# 60W_FM_PA.net
KiCad netlist of a schematic drawn in EAGLE
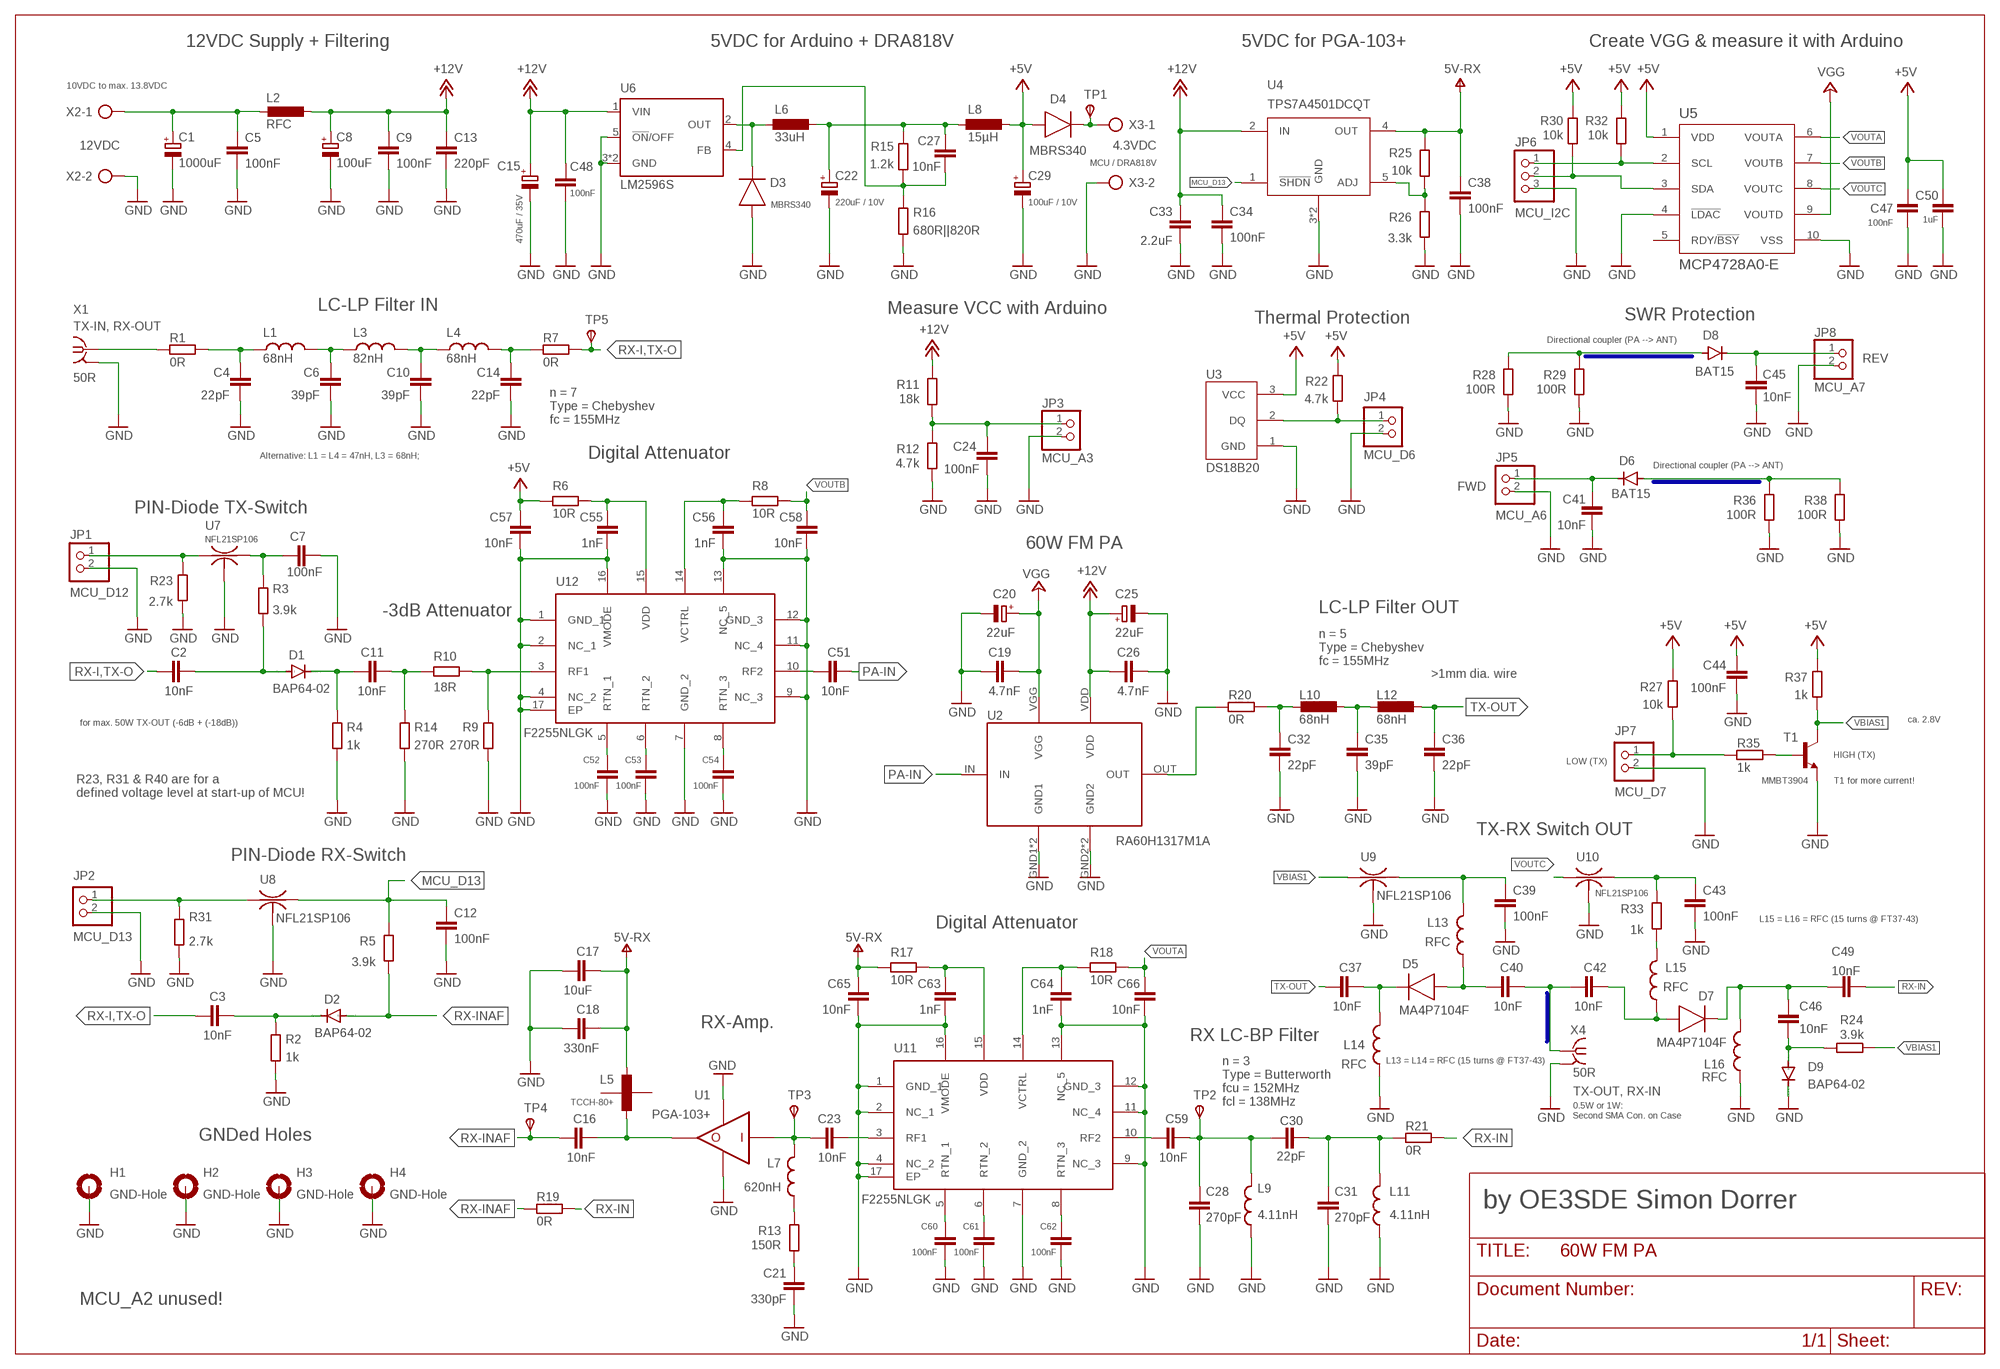
[diagram p0: schematic, sheet 1]

(export (version "E")
  (design (tool "Eeschema 10.0.6"))
  (components
    (comp (ref "C1")
      (value "1000uF")
      (footprint "eagle-import:CAPAE1030X1050N")
      (libsource (lib "eagle-import") (part "C-POLECAP-10.5MM_"))
    )
    (comp (ref "C2")
      (value "10nF")
      (footprint "eagle-import:CAPC2012X110")
      (libsource (lib "eagle-import") (part "CCHIP-0805(2012-METRIC)_"))
    )
    (comp (ref "C3")
      (value "10nF")
      (footprint "eagle-import:CAPC2012X110")
      (libsource (lib "eagle-import") (part "CCHIP-0805(2012-METRIC)_"))
    )
    (comp (ref "C4")
      (value "22pF")
      (footprint "eagle-import:CAPC2012X110")
      (libsource (lib "eagle-import") (part "CCHIP-0805(2012-METRIC)_"))
    )
    (comp (ref "C5")
      (value "100nF")
      (footprint "eagle-import:CAPC2012X110")
      (libsource (lib "eagle-import") (part "CCHIP-0805(2012-METRIC)_"))
    )
    (comp (ref "C6")
      (value "39pF")
      (footprint "eagle-import:CAPC2012X110")
      (libsource (lib "eagle-import") (part "CCHIP-0805(2012-METRIC)_"))
    )
    (comp (ref "C7")
      (value "100nF")
      (footprint "eagle-import:CAPC2012X110")
      (libsource (lib "eagle-import") (part "CCHIP-0805(2012-METRIC)_"))
    )
    (comp (ref "C8")
      (value "100uF")
      (footprint "eagle-import:CAPAE1030X1050N")
      (libsource (lib "eagle-import") (part "C-POLECAP-10.5MM_"))
    )
    (comp (ref "C9")
      (value "100nF")
      (footprint "eagle-import:CAPC2012X110")
      (libsource (lib "eagle-import") (part "CCHIP-0805(2012-METRIC)_"))
    )
    (comp (ref "C10")
      (value "39pF")
      (footprint "eagle-import:CAPC2012X110")
      (libsource (lib "eagle-import") (part "CCHIP-0805(2012-METRIC)_"))
    )
    (comp (ref "C11")
      (value "10nF")
      (footprint "eagle-import:CAPC2012X110")
      (libsource (lib "eagle-import") (part "CCHIP-0805(2012-METRIC)_"))
    )
    (comp (ref "C12")
      (value "100nF")
      (footprint "eagle-import:CAPC2012X110")
      (libsource (lib "eagle-import") (part "CCHIP-0805(2012-METRIC)_"))
    )
    (comp (ref "C13")
      (value "220pF")
      (footprint "eagle-import:CAPC2012X110")
      (libsource (lib "eagle-import") (part "CCHIP-0805(2012-METRIC)_"))
    )
    (comp (ref "C14")
      (value "22pF")
      (footprint "eagle-import:CAPC2012X110")
      (libsource (lib "eagle-import") (part "CCHIP-0805(2012-METRIC)_"))
    )
    (comp (ref "C15")
      (value "470uF / 35V")
      (footprint "eagle-import:CAPAE1030X1050N")
      (libsource (lib "eagle-import") (part "C-POLECAP-10.5MM_"))
    )
    (comp (ref "C16")
      (value "10nF")
      (footprint "eagle-import:CAPC2012X110")
      (libsource (lib "eagle-import") (part "CCHIP-0805(2012-METRIC)_"))
    )
    (comp (ref "C17")
      (value "10uF")
      (footprint "eagle-import:CAPC2012X110")
      (libsource (lib "eagle-import") (part "CCHIP-0805(2012-METRIC)_"))
    )
    (comp (ref "C18")
      (value "330nF")
      (footprint "eagle-import:CAPC2012X110")
      (libsource (lib "eagle-import") (part "CCHIP-0805(2012-METRIC)_"))
    )
    (comp (ref "C19")
      (value "4.7nF")
      (footprint "eagle-import:CAPC2012X110")
      (libsource (lib "eagle-import") (part "CCHIP-0805(2012-METRIC)_"))
    )
    (comp (ref "C20")
      (value "22uF")
      (footprint "eagle-import:SMC_D")
      (libsource (lib "eagle-import") (part "CPOL-EUSMCD"))
    )
    (comp (ref "C21")
      (value "330pF")
      (footprint "eagle-import:CAPC2012X110")
      (libsource (lib "eagle-import") (part "CCHIP-0805(2012-METRIC)_"))
    )
    (comp (ref "C22")
      (value "220uF / 10V")
      (footprint "eagle-import:CAPMP7343X310N")
      (libsource (lib "eagle-import") (part "C-POLTANTALUM-2917(7343-METRIC)_"))
    )
    (comp (ref "C23")
      (value "10nF")
      (footprint "eagle-import:CAPC2012X110")
      (libsource (lib "eagle-import") (part "CCHIP-0805(2012-METRIC)_"))
    )
    (comp (ref "C24")
      (value "100nF")
      (footprint "eagle-import:CAPC2012X110")
      (libsource (lib "eagle-import") (part "CCHIP-0805(2012-METRIC)_"))
    )
    (comp (ref "C25")
      (value "22uF")
      (footprint "eagle-import:SMC_D")
      (libsource (lib "eagle-import") (part "CPOL-EUSMCD"))
    )
    (comp (ref "C26")
      (value "4.7nF")
      (footprint "eagle-import:CAPC2012X110")
      (libsource (lib "eagle-import") (part "CCHIP-0805(2012-METRIC)_"))
    )
    (comp (ref "C27")
      (value "10nF")
      (footprint "eagle-import:CAPC2012X110")
      (libsource (lib "eagle-import") (part "CCHIP-0805(2012-METRIC)_"))
    )
    (comp (ref "C28")
      (value "270pF")
      (footprint "eagle-import:CAPC2012X110")
      (libsource (lib "eagle-import") (part "CCHIP-0805(2012-METRIC)_"))
    )
    (comp (ref "C29")
      (value "100uF / 10V")
      (footprint "eagle-import:CAPMP7343X310N")
      (libsource (lib "eagle-import") (part "C-POLTANTALUM-2917(7343-METRIC)_"))
    )
    (comp (ref "C30")
      (value "22pF")
      (footprint "eagle-import:CAPC2012X110")
      (libsource (lib "eagle-import") (part "CCHIP-0805(2012-METRIC)_"))
    )
    (comp (ref "C31")
      (value "270pF")
      (footprint "eagle-import:CAPC2012X110")
      (libsource (lib "eagle-import") (part "CCHIP-0805(2012-METRIC)_"))
    )
    (comp (ref "C32")
      (value "22pF")
      (footprint "eagle-import:CAPC3216X135")
      (libsource (lib "eagle-import") (part "CCHIP-1206(3216-METRIC)_"))
    )
    (comp (ref "C33")
      (value "2.2uF")
      (footprint "eagle-import:CAPC2012X110")
      (libsource (lib "eagle-import") (part "CCHIP-0805(2012-METRIC)_"))
    )
    (comp (ref "C34")
      (value "100nF")
      (footprint "eagle-import:CAPC2012X110")
      (libsource (lib "eagle-import") (part "CCHIP-0805(2012-METRIC)_"))
    )
    (comp (ref "C35")
      (value "39pF")
      (footprint "eagle-import:CAPC3216X135")
      (libsource (lib "eagle-import") (part "CCHIP-1206(3216-METRIC)_"))
    )
    (comp (ref "C36")
      (value "22pF")
      (footprint "eagle-import:CAPC3216X135")
      (libsource (lib "eagle-import") (part "CCHIP-1206(3216-METRIC)_"))
    )
    (comp (ref "C37")
      (value "10nF")
      (footprint "eagle-import:CAPC3216X135")
      (libsource (lib "eagle-import") (part "CCHIP-1206(3216-METRIC)_"))
    )
    (comp (ref "C38")
      (value "100nF")
      (footprint "eagle-import:CAPC2012X110")
      (libsource (lib "eagle-import") (part "CCHIP-0805(2012-METRIC)_"))
    )
    (comp (ref "C39")
      (value "100nF")
      (footprint "eagle-import:CAPC2012X110")
      (libsource (lib "eagle-import") (part "CCHIP-0805(2012-METRIC)_"))
    )
    (comp (ref "C40")
      (value "10nF")
      (footprint "eagle-import:CAPC3216X135")
      (libsource (lib "eagle-import") (part "CCHIP-1206(3216-METRIC)_"))
    )
    (comp (ref "C41")
      (value "10nF")
      (footprint "eagle-import:CAPC2012X110")
      (libsource (lib "eagle-import") (part "CCHIP-0805(2012-METRIC)_"))
    )
    (comp (ref "C42")
      (value "10nF")
      (footprint "eagle-import:CAPC3216X135")
      (libsource (lib "eagle-import") (part "CCHIP-1206(3216-METRIC)_"))
    )
    (comp (ref "C43")
      (value "100nF")
      (footprint "eagle-import:CAPC2012X110")
      (libsource (lib "eagle-import") (part "CCHIP-0805(2012-METRIC)_"))
    )
    (comp (ref "C44")
      (value "100nF")
      (footprint "eagle-import:CAPC2012X110")
      (libsource (lib "eagle-import") (part "CCHIP-0805(2012-METRIC)_"))
    )
    (comp (ref "C45")
      (value "10nF")
      (footprint "eagle-import:CAPC2012X110")
      (libsource (lib "eagle-import") (part "CCHIP-0805(2012-METRIC)_"))
    )
    (comp (ref "C46")
      (value "10nF")
      (footprint "eagle-import:CAPC2012X110")
      (libsource (lib "eagle-import") (part "CCHIP-0805(2012-METRIC)_"))
    )
    (comp (ref "C47")
      (value "100nF")
      (footprint "eagle-import:CAPC2012X110")
      (libsource (lib "eagle-import") (part "CCHIP-0805(2012-METRIC)_"))
    )
    (comp (ref "C48")
      (value "100nF")
      (footprint "eagle-import:CAPC2012X110")
      (libsource (lib "eagle-import") (part "CCHIP-0805(2012-METRIC)_"))
    )
    (comp (ref "C49")
      (value "10nF")
      (footprint "eagle-import:CAPC2012X110")
      (libsource (lib "eagle-import") (part "CCHIP-0805(2012-METRIC)_"))
    )
    (comp (ref "C50")
      (value "1uF")
      (footprint "eagle-import:CAPC2012X110")
      (libsource (lib "eagle-import") (part "CCHIP-0805(2012-METRIC)_"))
    )
    (comp (ref "C51")
      (value "10nF")
      (footprint "eagle-import:CAPC2012X110")
      (libsource (lib "eagle-import") (part "CCHIP-0805(2012-METRIC)_"))
    )
    (comp (ref "C52")
      (value "100nF")
      (footprint "eagle-import:CAPC1608X85")
      (libsource (lib "eagle-import") (part "CCHIP-0603(1608-METRIC)_"))
    )
    (comp (ref "C53")
      (value "100nF")
      (footprint "eagle-import:CAPC1608X85")
      (libsource (lib "eagle-import") (part "CCHIP-0603(1608-METRIC)_"))
    )
    (comp (ref "C54")
      (value "100nF")
      (footprint "eagle-import:CAPC1608X85")
      (libsource (lib "eagle-import") (part "CCHIP-0603(1608-METRIC)_"))
    )
    (comp (ref "C55")
      (value "1nF")
      (footprint "eagle-import:CAPC2012X110")
      (libsource (lib "eagle-import") (part "CCHIP-0805(2012-METRIC)_"))
    )
    (comp (ref "C56")
      (value "1nF")
      (footprint "eagle-import:CAPC2012X110")
      (libsource (lib "eagle-import") (part "CCHIP-0805(2012-METRIC)_"))
    )
    (comp (ref "C57")
      (value "10nF")
      (footprint "eagle-import:CAPC2012X110")
      (libsource (lib "eagle-import") (part "CCHIP-0805(2012-METRIC)_"))
    )
    (comp (ref "C58")
      (value "10nF")
      (footprint "eagle-import:CAPC2012X110")
      (libsource (lib "eagle-import") (part "CCHIP-0805(2012-METRIC)_"))
    )
    (comp (ref "C59")
      (value "10nF")
      (footprint "eagle-import:CAPC2012X110")
      (libsource (lib "eagle-import") (part "CCHIP-0805(2012-METRIC)_"))
    )
    (comp (ref "C60")
      (value "100nF")
      (footprint "eagle-import:CAPC1608X85")
      (libsource (lib "eagle-import") (part "CCHIP-0603(1608-METRIC)_"))
    )
    (comp (ref "C61")
      (value "100nF")
      (footprint "eagle-import:CAPC1608X85")
      (libsource (lib "eagle-import") (part "CCHIP-0603(1608-METRIC)_"))
    )
    (comp (ref "C62")
      (value "100nF")
      (footprint "eagle-import:CAPC1608X85")
      (libsource (lib "eagle-import") (part "CCHIP-0603(1608-METRIC)_"))
    )
    (comp (ref "C63")
      (value "1nF")
      (footprint "eagle-import:CAPC2012X110")
      (libsource (lib "eagle-import") (part "CCHIP-0805(2012-METRIC)_"))
    )
    (comp (ref "C64")
      (value "1nF")
      (footprint "eagle-import:CAPC2012X110")
      (libsource (lib "eagle-import") (part "CCHIP-0805(2012-METRIC)_"))
    )
    (comp (ref "C65")
      (value "10nF")
      (footprint "eagle-import:CAPC2012X110")
      (libsource (lib "eagle-import") (part "CCHIP-0805(2012-METRIC)_"))
    )
    (comp (ref "C66")
      (value "10nF")
      (footprint "eagle-import:CAPC2012X110")
      (libsource (lib "eagle-import") (part "CCHIP-0805(2012-METRIC)_"))
    )
    (comp (ref "D1")
      (value "BAP64-02")
      (footprint "eagle-import:SOD523")
      (libsource (lib "eagle-import") (part "DIODE-SOD523"))
    )
    (comp (ref "D2")
      (value "BAP64-02")
      (footprint "eagle-import:SOD523")
      (libsource (lib "eagle-import") (part "DIODE-SOD523"))
    )
    (comp (ref "D3")
      (value "MBRS340")
      (footprint "eagle-import:DIOM7959X625N")
      (libsource (lib "eagle-import") (part "DIODEDO-214AB(SMC)"))
    )
    (comp (ref "D4")
      (value "MBRS340")
      (footprint "eagle-import:DIOM7959X625N")
      (libsource (lib "eagle-import") (part "DIODEDO-214AB(SMC)"))
    )
    (comp (ref "D5")
      (value "MA4P7104F")
      (footprint "eagle-import:SODFL5336X110")
      (libsource (lib "eagle-import") (part "DIODEDO-221-AA_"))
    )
    (comp (ref "D6")
      (value "BAT15")
      (footprint "eagle-import:SOD-323")
      (fields
        (field (name "DIGIKEY_PART_NUMBER") "1N4148WSFSTR-ND")
        (field (name "MANUFACTURER") "Diodes Incorporated")
        (field (name "MPN") "1N4148WS")
        (field (name "CREATED_BY") "PCBLayout.com")
      )
      (libsource (lib "eagle-import") (part "1N4148WS"))
    )
    (comp (ref "D7")
      (value "MA4P7104F")
      (footprint "eagle-import:SODFL5336X110")
      (libsource (lib "eagle-import") (part "DIODEDO-221-AA_"))
    )
    (comp (ref "D8")
      (value "BAT15")
      (footprint "eagle-import:SOD-323")
      (fields
        (field (name "DIGIKEY_PART_NUMBER") "1N4148WSFSTR-ND")
        (field (name "MANUFACTURER") "Diodes Incorporated")
        (field (name "MPN") "1N4148WS")
        (field (name "CREATED_BY") "PCBLayout.com")
      )
      (libsource (lib "eagle-import") (part "1N4148WS"))
    )
    (comp (ref "D9")
      (value "BAP64-02")
      (footprint "eagle-import:SOD523")
      (libsource (lib "eagle-import") (part "DIODE-SOD523"))
    )
    (comp (ref "H1")
      (value "GND-Hole")
      (footprint "eagle-import:3,0-PAD")
      (libsource (lib "eagle-import") (part "MOUNT-PAD-ROUND3.0"))
    )
    (comp (ref "H2")
      (value "GND-Hole")
      (footprint "eagle-import:3,0-PAD")
      (libsource (lib "eagle-import") (part "MOUNT-PAD-ROUND3.0"))
    )
    (comp (ref "H3")
      (value "GND-Hole")
      (footprint "eagle-import:3,0-PAD")
      (libsource (lib "eagle-import") (part "MOUNT-PAD-ROUND3.0"))
    )
    (comp (ref "H4")
      (value "GND-Hole")
      (footprint "eagle-import:3,0-PAD")
      (libsource (lib "eagle-import") (part "MOUNT-PAD-ROUND3.0"))
    )
    (comp (ref "JP1")
      (value "MCU_D12")
      (footprint "eagle-import:1X02")
      (libsource (lib "eagle-import") (part "PINHD-1X2"))
    )
    (comp (ref "JP2")
      (value "MCU_D13")
      (footprint "eagle-import:1X02")
      (libsource (lib "eagle-import") (part "PINHD-1X2"))
    )
    (comp (ref "JP3")
      (value "MCU_A3")
      (footprint "eagle-import:1X02")
      (libsource (lib "eagle-import") (part "PINHD-1X2"))
    )
    (comp (ref "JP4")
      (value "MCU_D6")
      (footprint "eagle-import:1X02")
      (libsource (lib "eagle-import") (part "PINHD-1X2"))
    )
    (comp (ref "JP5")
      (value "MCU_A6")
      (footprint "eagle-import:1X02")
      (libsource (lib "eagle-import") (part "PINHD-1X2"))
    )
    (comp (ref "JP6")
      (value "MCU_I2C")
      (footprint "eagle-import:1X03")
      (libsource (lib "eagle-import") (part "PINHD-1X3"))
    )
    (comp (ref "JP7")
      (value "MCU_D7")
      (footprint "eagle-import:1X02")
      (libsource (lib "eagle-import") (part "PINHD-1X2"))
    )
    (comp (ref "JP8")
      (value "MCU_A7")
      (footprint "eagle-import:1X02")
      (libsource (lib "eagle-import") (part "PINHD-1X2"))
    )
    (comp (ref "L1")
      (value "68nH")
      (footprint "eagle-import:INDC2009X120")
      (libsource (lib "eagle-import") (part "LCHIP-0805(2012-METRIC)_"))
    )
    (comp (ref "L2")
      (value "RFC")
      (footprint "eagle-import:T50-6SMD")
      (libsource (lib "eagle-import") (part "T50-6"))
    )
    (comp (ref "L3")
      (value "82nH")
      (footprint "eagle-import:INDC2009X120")
      (libsource (lib "eagle-import") (part "LCHIP-0805(2012-METRIC)_"))
    )
    (comp (ref "L4")
      (value "68nH")
      (footprint "eagle-import:INDC2009X120")
      (libsource (lib "eagle-import") (part "LCHIP-0805(2012-METRIC)_"))
    )
    (comp (ref "L5")
      (value "TCCH-80+")
      (footprint "eagle-import:TCCH-80")
      (libsource (lib "eagle-import") (part "TCCH-80+"))
    )
    (comp (ref "L6")
      (value "33uH")
      (footprint "eagle-import:1260")
      (libsource (lib "eagle-import") (part "L-EU"))
    )
    (comp (ref "L7")
      (value "620nH")
      (footprint "eagle-import:INDC2009X120")
      (libsource (lib "eagle-import") (part "LCHIP-0805(2012-METRIC)_"))
    )
    (comp (ref "L8")
      (value "15µH")
      (footprint "eagle-import:1260")
      (libsource (lib "eagle-import") (part "L-EU"))
    )
    (comp (ref "L9")
      (value "4.11nH")
      (footprint "eagle-import:INDC2009X120")
      (libsource (lib "eagle-import") (part "LCHIP-0805(2012-METRIC)_"))
    )
    (comp (ref "L10")
      (value "68nH")
      (footprint "eagle-import:T50-6SMD")
      (libsource (lib "eagle-import") (part "T50-6"))
    )
    (comp (ref "L11")
      (value "4.11nH")
      (footprint "eagle-import:INDC2009X120")
      (libsource (lib "eagle-import") (part "LCHIP-0805(2012-METRIC)_"))
    )
    (comp (ref "L12")
      (value "68nH")
      (footprint "eagle-import:T50-6SMD")
      (libsource (lib "eagle-import") (part "T50-6"))
    )
    (comp (ref "L13")
      (value "RFC")
      (footprint "eagle-import:INDC3216X190")
      (libsource (lib "eagle-import") (part "LCHIP-1206(3216-METRIC)_"))
    )
    (comp (ref "L14")
      (value "RFC")
      (footprint "eagle-import:INDC3216X190")
      (libsource (lib "eagle-import") (part "LCHIP-1206(3216-METRIC)_"))
    )
    (comp (ref "L15")
      (value "RFC")
      (footprint "eagle-import:INDC3216X190")
      (libsource (lib "eagle-import") (part "LCHIP-1206(3216-METRIC)_"))
    )
    (comp (ref "L16")
      (value "RFC")
      (footprint "eagle-import:INDC3216X190")
      (libsource (lib "eagle-import") (part "LCHIP-1206(3216-METRIC)_"))
    )
    (comp (ref "R1")
      (value "0R")
      (footprint "eagle-import:RESC2012X65")
      (libsource (lib "eagle-import") (part "RCHIP-0805(2012-METRIC)_"))
    )
    (comp (ref "R2")
      (value "1k")
      (footprint "eagle-import:RESC2012X65")
      (libsource (lib "eagle-import") (part "RCHIP-0805(2012-METRIC)_"))
    )
    (comp (ref "R3")
      (value "3.9k")
      (footprint "eagle-import:RESC2012X65")
      (libsource (lib "eagle-import") (part "RCHIP-0805(2012-METRIC)_"))
    )
    (comp (ref "R4")
      (value "1k")
      (footprint "eagle-import:RESC2012X65")
      (libsource (lib "eagle-import") (part "RCHIP-0805(2012-METRIC)_"))
    )
    (comp (ref "R5")
      (value "3.9k")
      (footprint "eagle-import:RESC2012X65")
      (libsource (lib "eagle-import") (part "RCHIP-0805(2012-METRIC)_"))
    )
    (comp (ref "R6")
      (value "10R")
      (footprint "eagle-import:RESC2012X65")
      (libsource (lib "eagle-import") (part "RCHIP-0805(2012-METRIC)_"))
    )
    (comp (ref "R7")
      (value "0R")
      (footprint "eagle-import:RESC2012X65")
      (libsource (lib "eagle-import") (part "RCHIP-0805(2012-METRIC)_"))
    )
    (comp (ref "R8")
      (value "10R")
      (footprint "eagle-import:RESC2012X65")
      (libsource (lib "eagle-import") (part "RCHIP-0805(2012-METRIC)_"))
    )
    (comp (ref "R9")
      (value "270R")
      (footprint "eagle-import:RESC2012X65")
      (libsource (lib "eagle-import") (part "RCHIP-0805(2012-METRIC)_"))
    )
    (comp (ref "R10")
      (value "18R")
      (footprint "eagle-import:RESC2012X65")
      (libsource (lib "eagle-import") (part "RCHIP-0805(2012-METRIC)_"))
    )
    (comp (ref "R11")
      (value "18k")
      (footprint "eagle-import:RESC2012X65")
      (libsource (lib "eagle-import") (part "RCHIP-0805(2012-METRIC)_"))
    )
    (comp (ref "R12")
      (value "4.7k")
      (footprint "eagle-import:RESC2012X65")
      (libsource (lib "eagle-import") (part "RCHIP-0805(2012-METRIC)_"))
    )
    (comp (ref "R13")
      (value "150R")
      (footprint "eagle-import:RESC2012X65")
      (libsource (lib "eagle-import") (part "RCHIP-0805(2012-METRIC)_"))
    )
    (comp (ref "R14")
      (value "270R")
      (footprint "eagle-import:RESC2012X65")
      (libsource (lib "eagle-import") (part "RCHIP-0805(2012-METRIC)_"))
    )
    (comp (ref "R15")
      (value "1.2k")
      (footprint "eagle-import:RESC2012X65")
      (libsource (lib "eagle-import") (part "RCHIP-0805(2012-METRIC)_"))
    )
    (comp (ref "R16")
      (value "680R||820R")
      (footprint "eagle-import:RESC2012X65")
      (libsource (lib "eagle-import") (part "RCHIP-0805(2012-METRIC)_"))
    )
    (comp (ref "R17")
      (value "10R")
      (footprint "eagle-import:RESC2012X65")
      (libsource (lib "eagle-import") (part "RCHIP-0805(2012-METRIC)_"))
    )
    (comp (ref "R18")
      (value "10R")
      (footprint "eagle-import:RESC2012X65")
      (libsource (lib "eagle-import") (part "RCHIP-0805(2012-METRIC)_"))
    )
    (comp (ref "R19")
      (value "0R")
      (footprint "eagle-import:RESC2012X65")
      (libsource (lib "eagle-import") (part "RCHIP-0805(2012-METRIC)_"))
    )
    (comp (ref "R20")
      (value "0R")
      (footprint "eagle-import:RESC3216X70")
      (libsource (lib "eagle-import") (part "RCHIP-1206(3216-METRIC)_"))
    )
    (comp (ref "R21")
      (value "0R")
      (footprint "eagle-import:RESC2012X65")
      (libsource (lib "eagle-import") (part "RCHIP-0805(2012-METRIC)_"))
    )
    (comp (ref "R22")
      (value "4.7k")
      (footprint "eagle-import:RESC2012X65")
      (libsource (lib "eagle-import") (part "RCHIP-0805(2012-METRIC)_"))
    )
    (comp (ref "R23")
      (value "2.7k")
      (footprint "eagle-import:RESC2012X65")
      (libsource (lib "eagle-import") (part "RCHIP-0805(2012-METRIC)_"))
    )
    (comp (ref "R24")
      (value "3.9k")
      (footprint "eagle-import:RESC2012X65")
      (libsource (lib "eagle-import") (part "RCHIP-0805(2012-METRIC)_"))
    )
    (comp (ref "R25")
      (value "10k")
      (footprint "eagle-import:RESC2012X65")
      (libsource (lib "eagle-import") (part "RCHIP-0805(2012-METRIC)_"))
    )
    (comp (ref "R26")
      (value "3.3k")
      (footprint "eagle-import:RESC2012X65")
      (libsource (lib "eagle-import") (part "RCHIP-0805(2012-METRIC)_"))
    )
    (comp (ref "R27")
      (value "10k")
      (footprint "eagle-import:RESC2012X65")
      (libsource (lib "eagle-import") (part "RCHIP-0805(2012-METRIC)_"))
    )
    (comp (ref "R28")
      (value "100R")
      (footprint "eagle-import:RESC2012X65")
      (libsource (lib "eagle-import") (part "RCHIP-0805(2012-METRIC)_"))
    )
    (comp (ref "R29")
      (value "100R")
      (footprint "eagle-import:RESC2012X65")
      (libsource (lib "eagle-import") (part "RCHIP-0805(2012-METRIC)_"))
    )
    (comp (ref "R30")
      (value "10k")
      (footprint "eagle-import:RESC2012X65")
      (libsource (lib "eagle-import") (part "RCHIP-0805(2012-METRIC)_"))
    )
    (comp (ref "R31")
      (value "2.7k")
      (footprint "eagle-import:RESC2012X65")
      (libsource (lib "eagle-import") (part "RCHIP-0805(2012-METRIC)_"))
    )
    (comp (ref "R32")
      (value "10k")
      (footprint "eagle-import:RESC2012X65")
      (libsource (lib "eagle-import") (part "RCHIP-0805(2012-METRIC)_"))
    )
    (comp (ref "R33")
      (value "1k")
      (footprint "eagle-import:RESC2012X65")
      (libsource (lib "eagle-import") (part "RCHIP-0805(2012-METRIC)_"))
    )
    (comp (ref "R35")
      (value "1k")
      (footprint "eagle-import:RESC2012X65")
      (libsource (lib "eagle-import") (part "RCHIP-0805(2012-METRIC)_"))
    )
    (comp (ref "R36")
      (value "100R")
      (footprint "eagle-import:RESC2012X65")
      (libsource (lib "eagle-import") (part "RCHIP-0805(2012-METRIC)_"))
    )
    (comp (ref "R37")
      (value "1k")
      (footprint "eagle-import:RESC2012X65")
      (libsource (lib "eagle-import") (part "RCHIP-0805(2012-METRIC)_"))
    )
    (comp (ref "R38")
      (value "100R")
      (footprint "eagle-import:RESC2012X65")
      (libsource (lib "eagle-import") (part "RCHIP-0805(2012-METRIC)_"))
    )
    (comp (ref "T1")
      (value "MMBT3904")
      (footprint "eagle-import:SOT23")
      (fields
        (field (name "DIGIKEY_PART_NUMBER") "MMBT3904FSCT-ND")
        (field (name "MANUFACTURER") "ON Semiconductor")
        (field (name "CREATED_BY") "PCBLayout.com")
      )
      (libsource (lib "eagle-import") (part "MMBT3904"))
    )
    (comp (ref "TP1")
      (value "TPSTP10SQ")
      (footprint "eagle-import:TP10SQ")
      (libsource (lib "eagle-import") (part "TPSTP10SQ"))
    )
    (comp (ref "TP2")
      (value "TPSTP10SQ")
      (footprint "eagle-import:TP10SQ")
      (libsource (lib "eagle-import") (part "TPSTP10SQ"))
    )
    (comp (ref "TP3")
      (value "TPSTP10SQ")
      (footprint "eagle-import:TP10SQ")
      (libsource (lib "eagle-import") (part "TPSTP10SQ"))
    )
    (comp (ref "TP4")
      (value "TPSTP10SQ")
      (footprint "eagle-import:TP10SQ")
      (libsource (lib "eagle-import") (part "TPSTP10SQ"))
    )
    (comp (ref "TP5")
      (value "TPSTP10SQ")
      (footprint "eagle-import:TP10SQ")
      (libsource (lib "eagle-import") (part "TPSTP10SQ"))
    )
    (comp (ref "U1")
      (value "PGA-103+")
      (footprint "eagle-import:SOT89")
      (libsource (lib "eagle-import") (part "PGA-103+"))
    )
    (comp (ref "U2")
      (value "RA60H1317M1A")
      (footprint "eagle-import:RA60H1317M1A")
      (libsource (lib "eagle-import") (part "RA60H1317M1A"))
    )
    (comp (ref "U3")
      (value "DS18B20")
      (footprint "eagle-import:21-0248A_MXM")
      (fields (field (name "MANUFACTURER_PART_NUMBER") "DS1810-10"))
      (libsource (lib "eagle-import") (part "DS1810-10"))
    )
    (comp (ref "U4")
      (value "TPS7A4501DCQT")
      (footprint "eagle-import:DCQ6")
      (fields
        (field (name "GENERIC_PART_NUMBER") "TPS7A4533")
        (field (name "MANUFACTURER") "Texas Instruments")
      )
      (libsource (lib "eagle-import") (part "TPS7A4501DCQT"))
    )
    (comp (ref "U5")
      (value "MCP4728A0-E")
      (footprint "eagle-import:MSOP10_MC_MCH-M")
      (fields
        (field (name "MANUFACTURER_PART_NUMBER") "MCP4728A0-E/UN")
        (field (name "COPYRIGHT") "Copyright (C) 2018 Accelerated Designs. All rights reserved")
      )
      (libsource (lib "eagle-import") (part "MCP4728A0-E/UNMSOP10_MC_MCH-M"))
    )
    (comp (ref "U6")
      (value "LM2596S")
      (footprint "eagle-import:TO263-5")
      (fields (field (name "MF") "NATIONAL SEMICONDUCTOR") (field (name "MPN") "LM2596S-ADJ/NOPB"))
      (libsource (lib "eagle-import") (part "LM2596S"))
    )
    (comp (ref "U7")
      (value "NFL21SP106")
      (footprint "eagle-import:NFM21C")
      (libsource (lib "eagle-import") (part "NFL21SP106"))
    )
    (comp (ref "U8")
      (value "NFL21SP106")
      (footprint "eagle-import:NFM21C")
      (libsource (lib "eagle-import") (part "NFL21SP106"))
    )
    (comp (ref "U9")
      (value "NFL21SP106")
      (footprint "eagle-import:NFM21C")
      (libsource (lib "eagle-import") (part "NFL21SP106"))
    )
    (comp (ref "U10")
      (value "NFL21SP106")
      (footprint "eagle-import:NFM21C")
      (libsource (lib "eagle-import") (part "NFL21SP106"))
    )
    (comp (ref "U11")
      (value "F2255NLGK")
      (footprint "eagle-import:QFN50P300X300X100-17N")
      (fields (field (name "MOUSER_PART_NUMBER") "972-F2255NLGK"))
      (libsource (lib "eagle-import") (part "F2255NLGK"))
    )
    (comp (ref "U12")
      (value "F2255NLGK")
      (footprint "eagle-import:QFN50P300X300X100-17N")
      (fields (field (name "MOUSER_PART_NUMBER") "972-F2255NLGK"))
      (libsource (lib "eagle-import") (part "F2255NLGK"))
    )
    (comp (ref "X1")
      (value "TX-IN, RX-OUT")
      (footprint "eagle-import:J502-ND-142-0711-821_826")
      (fields (field (name "MF") "JOHNSON COMPONENTS") (field (name "MPN") "142-0711-821"))
      (libsource (lib "eagle-import") (part "SMA-142-0711-821/826"))
    )
    (comp (ref "X2")
      (value "12VDC")
      (footprint "eagle-import:AK300_2")
      (libsource (lib "eagle-import") (part "AK300/2"))
    )
    (comp (ref "X3")
      (value "4.3VDC")
      (footprint "eagle-import:AK300_2")
      (libsource (lib "eagle-import") (part "AK300/2"))
    )
    (comp (ref "X4")
      (value "TX-OUT, RX-IN")
      (footprint "eagle-import:J502-ND-142-0711-821_826")
      (fields (field (name "MF") "JOHNSON COMPONENTS") (field (name "MPN") "142-0711-821"))
      (libsource (lib "eagle-import") (part "SMA-142-0711-821/826"))
    )
  )
  (nets
    (net (code "4") (name "+5V") (class "Default")
      (node (ref "C29") (pin "1") (pinfunction "+_1") (pintype "passive"))
      (node (ref "C44") (pin "2") (pinfunction "2_2") (pintype "passive"))
      (node (ref "C47") (pin "2") (pinfunction "2_2") (pintype "passive"))
      (node (ref "C50") (pin "2") (pinfunction "2_2") (pintype "passive"))
      (node (ref "C57") (pin "1") (pinfunction "1_1") (pintype "passive"))
      (node (ref "D4") (pin "1") (pinfunction "A_1") (pintype "passive"))
      (node (ref "L8") (pin "-") (pinfunction "2_-") (pintype "passive"))
      (node (ref "R22") (pin "2") (pinfunction "2_2") (pintype "passive"))
      (node (ref "R27") (pin "1") (pinfunction "1_1") (pintype "passive"))
      (node (ref "R30") (pin "1") (pinfunction "1_1") (pintype "passive"))
      (node (ref "R32") (pin "1") (pinfunction "1_1") (pintype "passive"))
      (node (ref "R37") (pin "1") (pinfunction "1_1") (pintype "passive"))
      (node (ref "R6") (pin "1") (pinfunction "1_1") (pintype "passive"))
      (node (ref "U3") (pin "3") (pinfunction "VCC_3") (pintype "power_in"))
      (node (ref "U5") (pin "1") (pinfunction "VDD_1") (pintype "power_in"))
    )
    (net (code "5") (name "+12V") (class "Default")
      (node (ref "C13") (pin "2") (pinfunction "2_2") (pintype "passive"))
      (node (ref "C15") (pin "1") (pinfunction "+_1") (pintype "passive"))
      (node (ref "C25") (pin "+") (pinfunction "+_+") (pintype "passive"))
      (node (ref "C26") (pin "1") (pinfunction "1_1") (pintype "passive"))
      (node (ref "C33") (pin "2") (pinfunction "2_2") (pintype "passive"))
      (node (ref "C34") (pin "2") (pinfunction "2_2") (pintype "passive"))
      (node (ref "C48") (pin "2") (pinfunction "2_2") (pintype "passive"))
      (node (ref "C8") (pin "1") (pinfunction "+_1") (pintype "passive"))
      (node (ref "C9") (pin "2") (pinfunction "2_2") (pintype "passive"))
      (node (ref "L2") (pin "P$2") (pinfunction "2_P$2") (pintype "passive"))
      (node (ref "R11") (pin "2") (pinfunction "2_2") (pintype "passive"))
      (node (ref "U2") (pin "VDD") (pinfunction "VDD_VDD") (pintype "power_in"))
      (node (ref "U4") (pin "2") (pinfunction "IN_2") (pintype "input"))
      (node (ref "U6") (pin "1") (pinfunction "VIN_1") (pintype "input"))
    )
    (net (code "7") (name "5V-RX") (class "Default")
      (node (ref "C17") (pin "1") (pinfunction "1_1") (pintype "passive"))
      (node (ref "C18") (pin "1") (pinfunction "1_1") (pintype "passive"))
      (node (ref "C38") (pin "2") (pinfunction "2_2") (pintype "passive"))
      (node (ref "C65") (pin "1") (pinfunction "1_1") (pintype "passive"))
      (node (ref "L5") (pin "DC") (pinfunction "DC_DC") (pintype "passive"))
      (node (ref "R17") (pin "1") (pinfunction "1_1") (pintype "passive"))
      (node (ref "R25") (pin "1") (pinfunction "1_1") (pintype "passive"))
      (node (ref "U4") (pin "4") (pinfunction "OUT_4") (pintype "output"))
    )
    (net (code "8") (name "GND") (class "Default")
      (node (ref "C1") (pin "2") (pinfunction "-_2") (pintype "passive"))
      (node (ref "C10") (pin "2") (pinfunction "2_2") (pintype "passive"))
      (node (ref "C12") (pin "1") (pinfunction "1_1") (pintype "passive"))
      (node (ref "C13") (pin "1") (pinfunction "1_1") (pintype "passive"))
      (node (ref "C14") (pin "2") (pinfunction "2_2") (pintype "passive"))
      (node (ref "C15") (pin "2") (pinfunction "-_2") (pintype "passive"))
      (node (ref "C17") (pin "2") (pinfunction "2_2") (pintype "passive"))
      (node (ref "C18") (pin "2") (pinfunction "2_2") (pintype "passive"))
      (node (ref "C19") (pin "1") (pinfunction "1_1") (pintype "passive"))
      (node (ref "C20") (pin "-") (pinfunction "-_-") (pintype "passive"))
      (node (ref "C21") (pin "1") (pinfunction "1_1") (pintype "passive"))
      (node (ref "C22") (pin "2") (pinfunction "-_2") (pintype "passive"))
      (node (ref "C24") (pin "1") (pinfunction "1_1") (pintype "passive"))
      (node (ref "C25") (pin "-") (pinfunction "-_-") (pintype "passive"))
      (node (ref "C26") (pin "2") (pinfunction "2_2") (pintype "passive"))
      (node (ref "C28") (pin "2") (pinfunction "2_2") (pintype "passive"))
      (node (ref "C29") (pin "2") (pinfunction "-_2") (pintype "passive"))
      (node (ref "C31") (pin "2") (pinfunction "2_2") (pintype "passive"))
      (node (ref "C32") (pin "2") (pinfunction "2_2") (pintype "passive"))
      (node (ref "C33") (pin "1") (pinfunction "1_1") (pintype "passive"))
      (node (ref "C34") (pin "1") (pinfunction "1_1") (pintype "passive"))
      (node (ref "C35") (pin "2") (pinfunction "2_2") (pintype "passive"))
      (node (ref "C36") (pin "2") (pinfunction "2_2") (pintype "passive"))
      (node (ref "C38") (pin "1") (pinfunction "1_1") (pintype "passive"))
      (node (ref "C39") (pin "1") (pinfunction "1_1") (pintype "passive"))
      (node (ref "C4") (pin "2") (pinfunction "2_2") (pintype "passive"))
      (node (ref "C41") (pin "2") (pinfunction "2_2") (pintype "passive"))
      (node (ref "C43") (pin "1") (pinfunction "1_1") (pintype "passive"))
      (node (ref "C44") (pin "1") (pinfunction "1_1") (pintype "passive"))
      (node (ref "C45") (pin "2") (pinfunction "2_2") (pintype "passive"))
      (node (ref "C47") (pin "1") (pinfunction "1_1") (pintype "passive"))
      (node (ref "C48") (pin "1") (pinfunction "1_1") (pintype "passive"))
      (node (ref "C5") (pin "1") (pinfunction "1_1") (pintype "passive"))
      (node (ref "C50") (pin "1") (pinfunction "1_1") (pintype "passive"))
      (node (ref "C52") (pin "2") (pinfunction "2_2") (pintype "passive"))
      (node (ref "C53") (pin "2") (pinfunction "2_2") (pintype "passive"))
      (node (ref "C54") (pin "2") (pinfunction "2_2") (pintype "passive"))
      (node (ref "C55") (pin "2") (pinfunction "2_2") (pintype "passive"))
      (node (ref "C56") (pin "2") (pinfunction "2_2") (pintype "passive"))
      (node (ref "C57") (pin "2") (pinfunction "2_2") (pintype "passive"))
      (node (ref "C58") (pin "2") (pinfunction "2_2") (pintype "passive"))
      (node (ref "C6") (pin "2") (pinfunction "2_2") (pintype "passive"))
      (node (ref "C60") (pin "2") (pinfunction "2_2") (pintype "passive"))
      (node (ref "C61") (pin "2") (pinfunction "2_2") (pintype "passive"))
      (node (ref "C62") (pin "2") (pinfunction "2_2") (pintype "passive"))
      (node (ref "C63") (pin "2") (pinfunction "2_2") (pintype "passive"))
      (node (ref "C64") (pin "2") (pinfunction "2_2") (pintype "passive"))
      (node (ref "C65") (pin "2") (pinfunction "2_2") (pintype "passive"))
      (node (ref "C66") (pin "2") (pinfunction "2_2") (pintype "passive"))
      (node (ref "C7") (pin "1") (pinfunction "1_1") (pintype "passive"))
      (node (ref "C8") (pin "2") (pinfunction "-_2") (pintype "passive"))
      (node (ref "C9") (pin "1") (pinfunction "1_1") (pintype "passive"))
      (node (ref "D3") (pin "1") (pinfunction "A_1") (pintype "passive"))
      (node (ref "D9") (pin "C") (pinfunction "C_C") (pintype "passive"))
      (node (ref "H1") (pin "B3,0") (pinfunction "MOUNT_B3,0") (pintype "passive"))
      (node (ref "H2") (pin "B3,0") (pinfunction "MOUNT_B3,0") (pintype "passive"))
      (node (ref "H3") (pin "B3,0") (pinfunction "MOUNT_B3,0") (pintype "passive"))
      (node (ref "H4") (pin "B3,0") (pinfunction "MOUNT_B3,0") (pintype "passive"))
      (node (ref "JP1") (pin "2") (pinfunction "2_2") (pintype "passive"))
      (node (ref "JP2") (pin "2") (pinfunction "2_2") (pintype "passive"))
      (node (ref "JP3") (pin "2") (pinfunction "2_2") (pintype "passive"))
      (node (ref "JP4") (pin "2") (pinfunction "2_2") (pintype "passive"))
      (node (ref "JP5") (pin "2") (pinfunction "2_2") (pintype "passive"))
      (node (ref "JP6") (pin "3") (pinfunction "3_3") (pintype "passive"))
      (node (ref "JP7") (pin "2") (pinfunction "2_2") (pintype "passive"))
      (node (ref "JP8") (pin "2") (pinfunction "2_2") (pintype "passive"))
      (node (ref "L11") (pin "1") (pinfunction "1_1") (pintype "passive"))
      (node (ref "L14") (pin "1") (pinfunction "1_1") (pintype "passive"))
      (node (ref "L16") (pin "1") (pinfunction "1_1") (pintype "passive"))
      (node (ref "L9") (pin "1") (pinfunction "1_1") (pintype "passive"))
      (node (ref "R12") (pin "1") (pinfunction "1_1") (pintype "passive"))
      (node (ref "R14") (pin "2") (pinfunction "2_2") (pintype "passive"))
      (node (ref "R16") (pin "1") (pinfunction "1_1") (pintype "passive"))
      (node (ref "R2") (pin "2") (pinfunction "2_2") (pintype "passive"))
      (node (ref "R23") (pin "2") (pinfunction "2_2") (pintype "passive"))
      (node (ref "R26") (pin "2") (pinfunction "2_2") (pintype "passive"))
      (node (ref "R28") (pin "1") (pinfunction "1_1") (pintype "passive"))
      (node (ref "R29") (pin "1") (pinfunction "1_1") (pintype "passive"))
      (node (ref "R31") (pin "2") (pinfunction "2_2") (pintype "passive"))
      (node (ref "R36") (pin "1") (pinfunction "1_1") (pintype "passive"))
      (node (ref "R38") (pin "1") (pinfunction "1_1") (pintype "passive"))
      (node (ref "R4") (pin "2") (pinfunction "2_2") (pintype "passive"))
      (node (ref "R9") (pin "2") (pinfunction "2_2") (pintype "passive"))
      (node (ref "T1") (pin "2") (pinfunction "E_2") (pintype "passive"))
      (node (ref "U1") (pin "2") (pinfunction "GND1_2") (pintype "power_in"))
      (node (ref "U1") (pin "2@1") (pinfunction "GND2_2@1") (pintype "power_in"))
      (node (ref "U10") (pin "2@1") (pinfunction "2_2@1") (pintype "passive"))
      (node (ref "U10") (pin "2@2") (pinfunction "2_2@2") (pintype "passive"))
      (node (ref "U11") (pin "1") (pinfunction "GND_1_1") (pintype "bidirectional"))
      (node (ref "U11") (pin "11") (pinfunction "NC_4_11") (pintype "bidirectional"))
      (node (ref "U11") (pin "12") (pinfunction "GND_3_12") (pintype "bidirectional"))
      (node (ref "U11") (pin "13") (pinfunction "NC_5_13") (pintype "bidirectional"))
      (node (ref "U11") (pin "16") (pinfunction "VMODE_16") (pintype "bidirectional"))
      (node (ref "U11") (pin "17") (pinfunction "EP_17") (pintype "bidirectional"))
      (node (ref "U11") (pin "2") (pinfunction "NC_1_2") (pintype "bidirectional"))
      (node (ref "U11") (pin "4") (pinfunction "NC_2_4") (pintype "bidirectional"))
      (node (ref "U11") (pin "7") (pinfunction "GND_2_7") (pintype "bidirectional"))
      (node (ref "U11") (pin "9") (pinfunction "NC_3_9") (pintype "bidirectional"))
      (node (ref "U12") (pin "1") (pinfunction "GND_1_1") (pintype "bidirectional"))
      (node (ref "U12") (pin "11") (pinfunction "NC_4_11") (pintype "bidirectional"))
      (node (ref "U12") (pin "12") (pinfunction "GND_3_12") (pintype "bidirectional"))
      (node (ref "U12") (pin "13") (pinfunction "NC_5_13") (pintype "bidirectional"))
      (node (ref "U12") (pin "16") (pinfunction "VMODE_16") (pintype "bidirectional"))
      (node (ref "U12") (pin "17") (pinfunction "EP_17") (pintype "bidirectional"))
      (node (ref "U12") (pin "2") (pinfunction "NC_1_2") (pintype "bidirectional"))
      (node (ref "U12") (pin "4") (pinfunction "NC_2_4") (pintype "bidirectional"))
      (node (ref "U12") (pin "7") (pinfunction "GND_2_7") (pintype "bidirectional"))
      (node (ref "U12") (pin "9") (pinfunction "NC_3_9") (pintype "bidirectional"))
      (node (ref "U2") (pin "GND1") (pinfunction "GND1_GND1") (pintype "power_in"))
      (node (ref "U2") (pin "GND2") (pinfunction "GND2_GND2") (pintype "power_in"))
      (node (ref "U2") (pin "GND3") (pinfunction "GND1_GND3") (pintype "power_in"))
      (node (ref "U2") (pin "GND4") (pinfunction "GND2_GND4") (pintype "power_in"))
      (node (ref "U3") (pin "1") (pinfunction "GND_1") (pintype "power_in"))
      (node (ref "U4") (pin "3") (pinfunction "GND_3") (pintype "power_in"))
      (node (ref "U4") (pin "6") (pinfunction "GND_6") (pintype "power_in"))
      (node (ref "U5") (pin "10") (pinfunction "VSS_10") (pintype "power_in"))
      (node (ref "U5") (pin "4") (pinfunction "~{LDAC}_4") (pintype "input"))
      (node (ref "U6") (pin "3") (pinfunction "GND_3") (pintype "power_in"))
      (node (ref "U6") (pin "5") (pinfunction "~{ON}/OFF_5") (pintype "input"))
      (node (ref "U6") (pin "6") (pinfunction "GND_6") (pintype "power_in"))
      (node (ref "U7") (pin "2@1") (pinfunction "2_2@1") (pintype "passive"))
      (node (ref "U7") (pin "2@2") (pinfunction "2_2@2") (pintype "passive"))
      (node (ref "U8") (pin "2@1") (pinfunction "2_2@1") (pintype "passive"))
      (node (ref "U8") (pin "2@2") (pinfunction "2_2@2") (pintype "passive"))
      (node (ref "U9") (pin "2@1") (pinfunction "2_2@1") (pintype "passive"))
      (node (ref "U9") (pin "2@2") (pinfunction "2_2@2") (pintype "passive"))
      (node (ref "X1") (pin "G@1") (pinfunction "2_G@1") (pintype "passive"))
      (node (ref "X1") (pin "G@2") (pinfunction "2_G@2") (pintype "passive"))
      (node (ref "X1") (pin "G@3") (pinfunction "2_G@3") (pintype "passive"))
      (node (ref "X1") (pin "G@4") (pinfunction "2_G@4") (pintype "passive"))
      (node (ref "X2") (pin "2") (pinfunction "KL_2") (pintype "passive"))
      (node (ref "X3") (pin "2") (pinfunction "KL_2") (pintype "passive"))
      (node (ref "X4") (pin "G@1") (pinfunction "2_G@1") (pintype "passive"))
      (node (ref "X4") (pin "G@2") (pinfunction "2_G@2") (pintype "passive"))
      (node (ref "X4") (pin "G@3") (pinfunction "2_G@3") (pintype "passive"))
      (node (ref "X4") (pin "G@4") (pinfunction "2_G@4") (pintype "passive"))
    )
    (net (code "9") (name "MCU_D13") (class "Default")
      (node (ref "C12") (pin "2") (pinfunction "2_2") (pintype "passive"))
      (node (ref "R5") (pin "1") (pinfunction "1_1") (pintype "passive"))
      (node (ref "U4") (pin "1") (pinfunction "~{SHDN}_1") (pintype "passive"))
      (node (ref "U8") (pin "3") (pinfunction "3_3") (pintype "passive"))
    )
    (net (code "10") (name "Net-(C1-+)") (class "Default")
      (node (ref "C1") (pin "1") (pinfunction "+_1") (pintype "passive"))
      (node (ref "C5") (pin "2") (pinfunction "2_2") (pintype "passive"))
      (node (ref "L2") (pin "P$1") (pinfunction "1_P$1") (pintype "passive"))
      (node (ref "X2") (pin "1") (pinfunction "KL_1") (pintype "passive"))
    )
    (net (code "11") (name "Net-(C2-Pad1)") (class "Default")
      (node (ref "C2") (pin "1") (pinfunction "1_1") (pintype "passive"))
      (node (ref "D1") (pin "A") (pinfunction "A_A") (pintype "passive"))
      (node (ref "R3") (pin "2") (pinfunction "2_2") (pintype "passive"))
    )
    (net (code "12") (name "Net-(C3-Pad1)") (class "Default")
      (node (ref "C3") (pin "1") (pinfunction "1_1") (pintype "passive"))
      (node (ref "D2") (pin "C") (pinfunction "C_C") (pintype "passive"))
      (node (ref "R2") (pin "1") (pinfunction "1_1") (pintype "passive"))
    )
    (net (code "13") (name "Net-(C4-Pad1)") (class "Default")
      (node (ref "C4") (pin "1") (pinfunction "1_1") (pintype "passive"))
      (node (ref "L1") (pin "1") (pinfunction "1_1") (pintype "passive"))
      (node (ref "R1") (pin "1") (pinfunction "1_1") (pintype "passive"))
    )
    (net (code "14") (name "Net-(C6-Pad1)") (class "Default")
      (node (ref "C6") (pin "1") (pinfunction "1_1") (pintype "passive"))
      (node (ref "L1") (pin "2") (pinfunction "2_2") (pintype "passive"))
      (node (ref "L3") (pin "1") (pinfunction "1_1") (pintype "passive"))
    )
    (net (code "15") (name "Net-(C7-Pad2)") (class "Default")
      (node (ref "C7") (pin "2") (pinfunction "2_2") (pintype "passive"))
      (node (ref "R3") (pin "1") (pinfunction "1_1") (pintype "passive"))
      (node (ref "U7") (pin "3") (pinfunction "3_3") (pintype "passive"))
    )
    (net (code "16") (name "Net-(C10-Pad1)") (class "Default")
      (node (ref "C10") (pin "1") (pinfunction "1_1") (pintype "passive"))
      (node (ref "L3") (pin "2") (pinfunction "2_2") (pintype "passive"))
      (node (ref "L4") (pin "1") (pinfunction "1_1") (pintype "passive"))
    )
    (net (code "17") (name "Net-(C11-Pad1)") (class "Default")
      (node (ref "C11") (pin "1") (pinfunction "1_1") (pintype "passive"))
      (node (ref "R10") (pin "1") (pinfunction "1_1") (pintype "passive"))
      (node (ref "R14") (pin "1") (pinfunction "1_1") (pintype "passive"))
    )
    (net (code "18") (name "Net-(C11-Pad2)") (class "Default")
      (node (ref "C11") (pin "2") (pinfunction "2_2") (pintype "passive"))
      (node (ref "D1") (pin "C") (pinfunction "C_C") (pintype "passive"))
      (node (ref "R4") (pin "1") (pinfunction "1_1") (pintype "passive"))
    )
    (net (code "19") (name "Net-(C14-Pad1)") (class "Default")
      (node (ref "C14") (pin "1") (pinfunction "1_1") (pintype "passive"))
      (node (ref "L4") (pin "2") (pinfunction "2_2") (pintype "passive"))
      (node (ref "R7") (pin "2") (pinfunction "2_2") (pintype "passive"))
    )
    (net (code "20") (name "Net-(C21-Pad2)") (class "Default")
      (node (ref "C21") (pin "2") (pinfunction "2_2") (pintype "passive"))
      (node (ref "R13") (pin "1") (pinfunction "1_1") (pintype "passive"))
    )
    (net (code "21") (name "Net-(C22-+)") (class "Default")
      (node (ref "C22") (pin "1") (pinfunction "+_1") (pintype "passive"))
      (node (ref "C27") (pin "2") (pinfunction "2_2") (pintype "passive"))
      (node (ref "L6") (pin "-") (pinfunction "2_-") (pintype "passive"))
      (node (ref "L8") (pin "+") (pinfunction "1_+") (pintype "passive"))
      (node (ref "R15") (pin "2") (pinfunction "2_2") (pintype "passive"))
    )
    (net (code "22") (name "Net-(C24-Pad2)") (class "Default")
      (node (ref "C24") (pin "2") (pinfunction "2_2") (pintype "passive"))
      (node (ref "JP3") (pin "1") (pinfunction "1_1") (pintype "passive"))
      (node (ref "R11") (pin "1") (pinfunction "1_1") (pintype "passive"))
      (node (ref "R12") (pin "2") (pinfunction "2_2") (pintype "passive"))
    )
    (net (code "23") (name "Net-(C30-Pad2)") (class "Default")
      (node (ref "C30") (pin "2") (pinfunction "2_2") (pintype "passive"))
      (node (ref "C31") (pin "1") (pinfunction "1_1") (pintype "passive"))
      (node (ref "L11") (pin "2") (pinfunction "2_2") (pintype "passive"))
      (node (ref "R21") (pin "2") (pinfunction "2_2") (pintype "passive"))
    )
    (net (code "24") (name "Net-(C39-Pad2)") (class "Default")
      (node (ref "C39") (pin "2") (pinfunction "2_2") (pintype "passive"))
      (node (ref "L13") (pin "2") (pinfunction "2_2") (pintype "passive"))
      (node (ref "U9") (pin "3") (pinfunction "3_3") (pintype "passive"))
    )
    (net (code "25") (name "Net-(C40-Pad1)") (class "Default")
      (node (ref "C40") (pin "1") (pinfunction "1_1") (pintype "passive"))
      (node (ref "C42") (pin "2") (pinfunction "2_2") (pintype "passive"))
      (node (ref "X4") (pin "1") (pinfunction "1_1") (pintype "passive"))
    )
    (net (code "26") (name "Net-(C41-Pad1)") (class "Default")
      (node (ref "C41") (pin "1") (pinfunction "1_1") (pintype "passive"))
      (node (ref "D6") (pin "C") (pinfunction "C_C") (pintype "passive"))
      (node (ref "JP5") (pin "1") (pinfunction "1_1") (pintype "passive"))
    )
    (net (code "27") (name "Net-(C43-Pad2)") (class "Default")
      (node (ref "C43") (pin "2") (pinfunction "2_2") (pintype "passive"))
      (node (ref "R33") (pin "1") (pinfunction "1_1") (pintype "passive"))
      (node (ref "U10") (pin "3") (pinfunction "3_3") (pintype "passive"))
    )
    (net (code "28") (name "Net-(C45-Pad1)") (class "Default")
      (node (ref "C45") (pin "1") (pinfunction "1_1") (pintype "passive"))
      (node (ref "D8") (pin "C") (pinfunction "C_C") (pintype "passive"))
      (node (ref "JP8") (pin "1") (pinfunction "1_1") (pintype "passive"))
    )
    (net (code "29") (name "Net-(C46-Pad2)") (class "Default")
      (node (ref "C46") (pin "2") (pinfunction "2_2") (pintype "passive"))
      (node (ref "D9") (pin "A") (pinfunction "A_A") (pintype "passive"))
      (node (ref "R24") (pin "2") (pinfunction "2_2") (pintype "passive"))
    )
    (net (code "30") (name "Net-(D3-C)") (class "Default")
      (node (ref "D3") (pin "2") (pinfunction "C_2") (pintype "passive"))
      (node (ref "L6") (pin "+") (pinfunction "1_+") (pintype "passive"))
      (node (ref "U6") (pin "2") (pinfunction "OUT_2") (pintype "output"))
    )
    (net (code "31") (name "Net-(D4-C)") (class "Default")
      (node (ref "D4") (pin "2") (pinfunction "C_2") (pintype "passive"))
      (node (ref "TP1") (pin "TP") (pinfunction "PP_TP") (pintype "input"))
      (node (ref "X3") (pin "1") (pinfunction "KL_1") (pintype "passive"))
    )
    (net (code "32") (name "Net-(D5-A)") (class "Default")
      (node (ref "C40") (pin "2") (pinfunction "2_2") (pintype "passive"))
      (node (ref "D5") (pin "1") (pinfunction "A_1") (pintype "passive"))
      (node (ref "L13") (pin "1") (pinfunction "1_1") (pintype "passive"))
    )
    (net (code "33") (name "Net-(D5-C)") (class "Default")
      (node (ref "C37") (pin "1") (pinfunction "1_1") (pintype "passive"))
      (node (ref "D5") (pin "2") (pinfunction "C_2") (pintype "passive"))
      (node (ref "L14") (pin "2") (pinfunction "2_2") (pintype "passive"))
    )
    (net (code "34") (name "Net-(D6-PadA)") (class "Default")
      (node (ref "D6") (pin "A") (pinfunction "A_A") (pintype "passive"))
      (node (ref "R36") (pin "2") (pinfunction "2_2") (pintype "passive"))
      (node (ref "R38") (pin "2") (pinfunction "2_2") (pintype "passive"))
    )
    (net (code "35") (name "Net-(D7-A)") (class "Default")
      (node (ref "C42") (pin "1") (pinfunction "1_1") (pintype "passive"))
      (node (ref "D7") (pin "1") (pinfunction "A_1") (pintype "passive"))
      (node (ref "L15") (pin "1") (pinfunction "1_1") (pintype "passive"))
    )
    (net (code "36") (name "Net-(D7-C)") (class "Default")
      (node (ref "C46") (pin "1") (pinfunction "1_1") (pintype "passive"))
      (node (ref "C49") (pin "2") (pinfunction "2_2") (pintype "passive"))
      (node (ref "D7") (pin "2") (pinfunction "C_2") (pintype "passive"))
      (node (ref "L16") (pin "2") (pinfunction "2_2") (pintype "passive"))
    )
    (net (code "37") (name "Net-(D8-PadA)") (class "Default")
      (node (ref "D8") (pin "A") (pinfunction "A_A") (pintype "passive"))
      (node (ref "R28") (pin "2") (pinfunction "2_2") (pintype "passive"))
      (node (ref "R29") (pin "2") (pinfunction "2_2") (pintype "passive"))
    )
    (net (code "38") (name "Net-(JP1-Pad1)") (class "Default")
      (node (ref "JP1") (pin "1") (pinfunction "1_1") (pintype "passive"))
      (node (ref "R23") (pin "1") (pinfunction "1_1") (pintype "passive"))
      (node (ref "U7") (pin "1") (pinfunction "1_1") (pintype "passive"))
    )
    (net (code "39") (name "Net-(JP2-Pad1)") (class "Default")
      (node (ref "JP2") (pin "1") (pinfunction "1_1") (pintype "passive"))
      (node (ref "R31") (pin "1") (pinfunction "1_1") (pintype "passive"))
      (node (ref "U8") (pin "1") (pinfunction "1_1") (pintype "passive"))
    )
    (net (code "40") (name "Net-(JP7-Pad1)") (class "Default")
      (node (ref "JP7") (pin "1") (pinfunction "1_1") (pintype "passive"))
      (node (ref "R27") (pin "2") (pinfunction "2_2") (pintype "passive"))
      (node (ref "R35") (pin "2") (pinfunction "2_2") (pintype "passive"))
    )
    (net (code "41") (name "Net-(L7-Pad1)") (class "Default")
      (node (ref "L7") (pin "1") (pinfunction "1_1") (pintype "passive"))
      (node (ref "R13") (pin "2") (pinfunction "2_2") (pintype "passive"))
    )
    (net (code "42") (name "Net-(L10-1)") (class "Default")
      (node (ref "C32") (pin "1") (pinfunction "1_1") (pintype "passive"))
      (node (ref "L10") (pin "P$1") (pinfunction "1_P$1") (pintype "passive"))
      (node (ref "R20") (pin "1") (pinfunction "1_1") (pintype "passive"))
    )
    (net (code "43") (name "Net-(L10-2)") (class "Default")
      (node (ref "C35") (pin "1") (pinfunction "1_1") (pintype "passive"))
      (node (ref "L10") (pin "P$2") (pinfunction "2_P$2") (pintype "passive"))
      (node (ref "L12") (pin "P$1") (pinfunction "1_P$1") (pintype "passive"))
    )
    (net (code "44") (name "Net-(L15-Pad2)") (class "Default")
      (node (ref "L15") (pin "2") (pinfunction "2_2") (pintype "passive"))
      (node (ref "R33") (pin "2") (pinfunction "2_2") (pintype "passive"))
    )
    (net (code "45") (name "Net-(R1-Pad2)") (class "Default")
      (node (ref "R1") (pin "2") (pinfunction "2_2") (pintype "passive"))
      (node (ref "X1") (pin "1") (pinfunction "1_1") (pintype "passive"))
    )
    (net (code "46") (name "Net-(R20-Pad2)") (class "Default")
      (node (ref "R20") (pin "2") (pinfunction "2_2") (pintype "passive"))
      (node (ref "U2") (pin "OUT") (pinfunction "OUT_OUT") (pintype "output"))
    )
    (net (code "47") (name "Net-(T1-B)") (class "Default")
      (node (ref "R35") (pin "1") (pinfunction "1_1") (pintype "passive"))
      (node (ref "T1") (pin "1") (pinfunction "B_1") (pintype "passive"))
    )
    (net (code "48") (name "Net-(TP2-PP)") (class "Default")
      (node (ref "C28") (pin "1") (pinfunction "1_1") (pintype "passive"))
      (node (ref "C30") (pin "1") (pinfunction "1_1") (pintype "passive"))
      (node (ref "C59") (pin "1") (pinfunction "1_1") (pintype "passive"))
      (node (ref "L9") (pin "2") (pinfunction "2_2") (pintype "passive"))
      (node (ref "TP2") (pin "TP") (pinfunction "PP_TP") (pintype "input"))
    )
    (net (code "49") (name "Net-(TP3-PP)") (class "Default")
      (node (ref "C23") (pin "2") (pinfunction "2_2") (pintype "passive"))
      (node (ref "L7") (pin "2") (pinfunction "2_2") (pintype "passive"))
      (node (ref "TP3") (pin "TP") (pinfunction "PP_TP") (pintype "input"))
      (node (ref "U1") (pin "1") (pinfunction "IN_1") (pintype "input"))
    )
    (net (code "50") (name "Net-(U1-OUT)") (class "Default")
      (node (ref "C16") (pin "1") (pinfunction "1_1") (pintype "passive"))
      (node (ref "L5") (pin "RF-DC") (pinfunction "RF-DC_RF-DC") (pintype "passive"))
      (node (ref "U1") (pin "3") (pinfunction "OUT_3") (pintype "output"))
    )
    (net (code "51") (name "Net-(U3-DQ)") (class "Default")
      (node (ref "JP4") (pin "1") (pinfunction "1_1") (pintype "passive"))
      (node (ref "R22") (pin "1") (pinfunction "1_1") (pintype "passive"))
      (node (ref "U3") (pin "2") (pinfunction "DQ_2") (pintype "output"))
    )
    (net (code "52") (name "Net-(U4-ADJ)") (class "Default")
      (node (ref "R25") (pin "2") (pinfunction "2_2") (pintype "passive"))
      (node (ref "R26") (pin "1") (pinfunction "1_1") (pintype "passive"))
      (node (ref "U4") (pin "5") (pinfunction "ADJ_5") (pintype "passive"))
    )
    (net (code "53") (name "Net-(U5-SCL)") (class "Default")
      (node (ref "JP6") (pin "1") (pinfunction "1_1") (pintype "passive"))
      (node (ref "R32") (pin "2") (pinfunction "2_2") (pintype "passive"))
      (node (ref "U5") (pin "2") (pinfunction "SCL_2") (pintype "input"))
    )
    (net (code "54") (name "Net-(U5-SDA)") (class "Default")
      (node (ref "JP6") (pin "2") (pinfunction "2_2") (pintype "passive"))
      (node (ref "R30") (pin "2") (pinfunction "2_2") (pintype "passive"))
      (node (ref "U5") (pin "3") (pinfunction "SDA_3") (pintype "bidirectional"))
    )
    (net (code "55") (name "Net-(U6-FB)") (class "Default")
      (node (ref "C27") (pin "1") (pinfunction "1_1") (pintype "passive"))
      (node (ref "R15") (pin "1") (pinfunction "1_1") (pintype "passive"))
      (node (ref "R16") (pin "2") (pinfunction "2_2") (pintype "passive"))
      (node (ref "U6") (pin "4") (pinfunction "FB_4") (pintype "input"))
    )
    (net (code "56") (name "Net-(U11-RF1)") (class "Default")
      (node (ref "C23") (pin "1") (pinfunction "1_1") (pintype "passive"))
      (node (ref "U11") (pin "3") (pinfunction "RF1_3") (pintype "bidirectional"))
    )
    (net (code "57") (name "Net-(U11-RF2)") (class "Default")
      (node (ref "C59") (pin "2") (pinfunction "2_2") (pintype "passive"))
      (node (ref "U11") (pin "10") (pinfunction "RF2_10") (pintype "bidirectional"))
    )
    (net (code "58") (name "Net-(U11-RTN_1)") (class "Default")
      (node (ref "C60") (pin "1") (pinfunction "1_1") (pintype "passive"))
      (node (ref "U11") (pin "5") (pinfunction "RTN_1_5") (pintype "bidirectional"))
    )
    (net (code "59") (name "Net-(U11-RTN_2)") (class "Default")
      (node (ref "C61") (pin "1") (pinfunction "1_1") (pintype "passive"))
      (node (ref "U11") (pin "6") (pinfunction "RTN_2_6") (pintype "bidirectional"))
    )
    (net (code "60") (name "Net-(U11-RTN_3)") (class "Default")
      (node (ref "C62") (pin "1") (pinfunction "1_1") (pintype "passive"))
      (node (ref "U11") (pin "8") (pinfunction "RTN_3_8") (pintype "bidirectional"))
    )
    (net (code "61") (name "Net-(U11-VCTRL)") (class "Default")
      (node (ref "C64") (pin "1") (pinfunction "1_1") (pintype "passive"))
      (node (ref "R18") (pin "1") (pinfunction "1_1") (pintype "passive"))
      (node (ref "U11") (pin "14") (pinfunction "VCTRL_14") (pintype "bidirectional"))
    )
    (net (code "62") (name "Net-(U11-VDD)") (class "Default")
      (node (ref "C63") (pin "1") (pinfunction "1_1") (pintype "passive"))
      (node (ref "R17") (pin "2") (pinfunction "2_2") (pintype "passive"))
      (node (ref "U11") (pin "15") (pinfunction "VDD_15") (pintype "bidirectional"))
    )
    (net (code "63") (name "Net-(U12-RF1)") (class "Default")
      (node (ref "R10") (pin "2") (pinfunction "2_2") (pintype "passive"))
      (node (ref "R9") (pin "1") (pinfunction "1_1") (pintype "passive"))
      (node (ref "U12") (pin "3") (pinfunction "RF1_3") (pintype "bidirectional"))
    )
    (net (code "64") (name "Net-(U12-RF2)") (class "Default")
      (node (ref "C51") (pin "2") (pinfunction "2_2") (pintype "passive"))
      (node (ref "U12") (pin "10") (pinfunction "RF2_10") (pintype "bidirectional"))
    )
    (net (code "65") (name "Net-(U12-RTN_1)") (class "Default")
      (node (ref "C52") (pin "1") (pinfunction "1_1") (pintype "passive"))
      (node (ref "U12") (pin "5") (pinfunction "RTN_1_5") (pintype "bidirectional"))
    )
    (net (code "66") (name "Net-(U12-RTN_2)") (class "Default")
      (node (ref "C53") (pin "1") (pinfunction "1_1") (pintype "passive"))
      (node (ref "U12") (pin "6") (pinfunction "RTN_2_6") (pintype "bidirectional"))
    )
    (net (code "67") (name "Net-(U12-RTN_3)") (class "Default")
      (node (ref "C54") (pin "1") (pinfunction "1_1") (pintype "passive"))
      (node (ref "U12") (pin "8") (pinfunction "RTN_3_8") (pintype "bidirectional"))
    )
    (net (code "68") (name "Net-(U12-VCTRL)") (class "Default")
      (node (ref "C56") (pin "1") (pinfunction "1_1") (pintype "passive"))
      (node (ref "R8") (pin "1") (pinfunction "1_1") (pintype "passive"))
      (node (ref "U12") (pin "14") (pinfunction "VCTRL_14") (pintype "bidirectional"))
    )
    (net (code "69") (name "Net-(U12-VDD)") (class "Default")
      (node (ref "C55") (pin "1") (pinfunction "1_1") (pintype "passive"))
      (node (ref "R6") (pin "2") (pinfunction "2_2") (pintype "passive"))
      (node (ref "U12") (pin "15") (pinfunction "VDD_15") (pintype "bidirectional"))
    )
    (net (code "70") (name "PA-IN") (class "Default")
      (node (ref "C51") (pin "1") (pinfunction "1_1") (pintype "passive"))
      (node (ref "U2") (pin "IN") (pinfunction "IN_IN") (pintype "input"))
    )
    (net (code "71") (name "RX-I,TX-O") (class "Default")
      (node (ref "C2") (pin "2") (pinfunction "2_2") (pintype "passive"))
      (node (ref "C3") (pin "2") (pinfunction "2_2") (pintype "passive"))
      (node (ref "R7") (pin "1") (pinfunction "1_1") (pintype "passive"))
      (node (ref "TP5") (pin "TP") (pinfunction "PP_TP") (pintype "input"))
    )
    (net (code "72") (name "RX-IN") (class "Default")
      (node (ref "C49") (pin "1") (pinfunction "1_1") (pintype "passive"))
      (node (ref "R19") (pin "1") (pinfunction "1_1") (pintype "passive"))
      (node (ref "R21") (pin "1") (pinfunction "1_1") (pintype "passive"))
    )
    (net (code "73") (name "RX-INAF") (class "Default")
      (node (ref "C16") (pin "2") (pinfunction "2_2") (pintype "passive"))
      (node (ref "D2") (pin "A") (pinfunction "A_A") (pintype "passive"))
      (node (ref "R19") (pin "2") (pinfunction "2_2") (pintype "passive"))
      (node (ref "R5") (pin "2") (pinfunction "2_2") (pintype "passive"))
      (node (ref "TP4") (pin "TP") (pinfunction "PP_TP") (pintype "input"))
    )
    (net (code "74") (name "TX-OUT") (class "Default")
      (node (ref "C36") (pin "1") (pinfunction "1_1") (pintype "passive"))
      (node (ref "C37") (pin "2") (pinfunction "2_2") (pintype "passive"))
      (node (ref "L12") (pin "P$2") (pinfunction "2_P$2") (pintype "passive"))
    )
    (net (code "75") (name "VBIAS1") (class "Default")
      (node (ref "R24") (pin "1") (pinfunction "1_1") (pintype "passive"))
      (node (ref "R37") (pin "2") (pinfunction "2_2") (pintype "passive"))
      (node (ref "T1") (pin "3") (pinfunction "C_3") (pintype "passive"))
      (node (ref "U9") (pin "1") (pinfunction "1_1") (pintype "passive"))
    )
    (net (code "76") (name "VGG") (class "Default")
      (node (ref "C19") (pin "2") (pinfunction "2_2") (pintype "passive"))
      (node (ref "C20") (pin "+") (pinfunction "+_+") (pintype "passive"))
      (node (ref "U2") (pin "VGG") (pinfunction "VGG_VGG") (pintype "power_in"))
      (node (ref "U5") (pin "9") (pinfunction "VOUTD_9") (pintype "output"))
    )
    (net (code "77") (name "VOUTA") (class "Default")
      (node (ref "C66") (pin "1") (pinfunction "1_1") (pintype "passive"))
      (node (ref "R18") (pin "2") (pinfunction "2_2") (pintype "passive"))
      (node (ref "U5") (pin "6") (pinfunction "VOUTA_6") (pintype "output"))
    )
    (net (code "78") (name "VOUTB") (class "Default")
      (node (ref "C58") (pin "1") (pinfunction "1_1") (pintype "passive"))
      (node (ref "R8") (pin "2") (pinfunction "2_2") (pintype "passive"))
      (node (ref "U5") (pin "7") (pinfunction "VOUTB_7") (pintype "output"))
    )
    (net (code "79") (name "VOUTC") (class "Default")
      (node (ref "U10") (pin "1") (pinfunction "1_1") (pintype "passive"))
      (node (ref "U5") (pin "8") (pinfunction "VOUTC_8") (pintype "output"))
    )
    (net (code "80") (name "unconnected-(L5-PadNC1)") (class "Default")
      (node (ref "L5") (pin "NC1") (pinfunction "NC1_NC1") (pintype "no_connect"))
    )
    (net (code "81") (name "unconnected-(L5-PadNC2)") (class "Default")
      (node (ref "L5") (pin "NC2") (pinfunction "NC2_NC2") (pintype "no_connect"))
    )
    (net (code "82") (name "unconnected-(U5-RDY{slash}~{BSY}-Pad5)") (class "Default")
      (node (ref "U5") (pin "5") (pinfunction "RDY/~{BSY}_5") (pintype "output"))
    )
  )
)
